# HIC15.net
KiCad netlist of a schematic drawn in Altium Designer
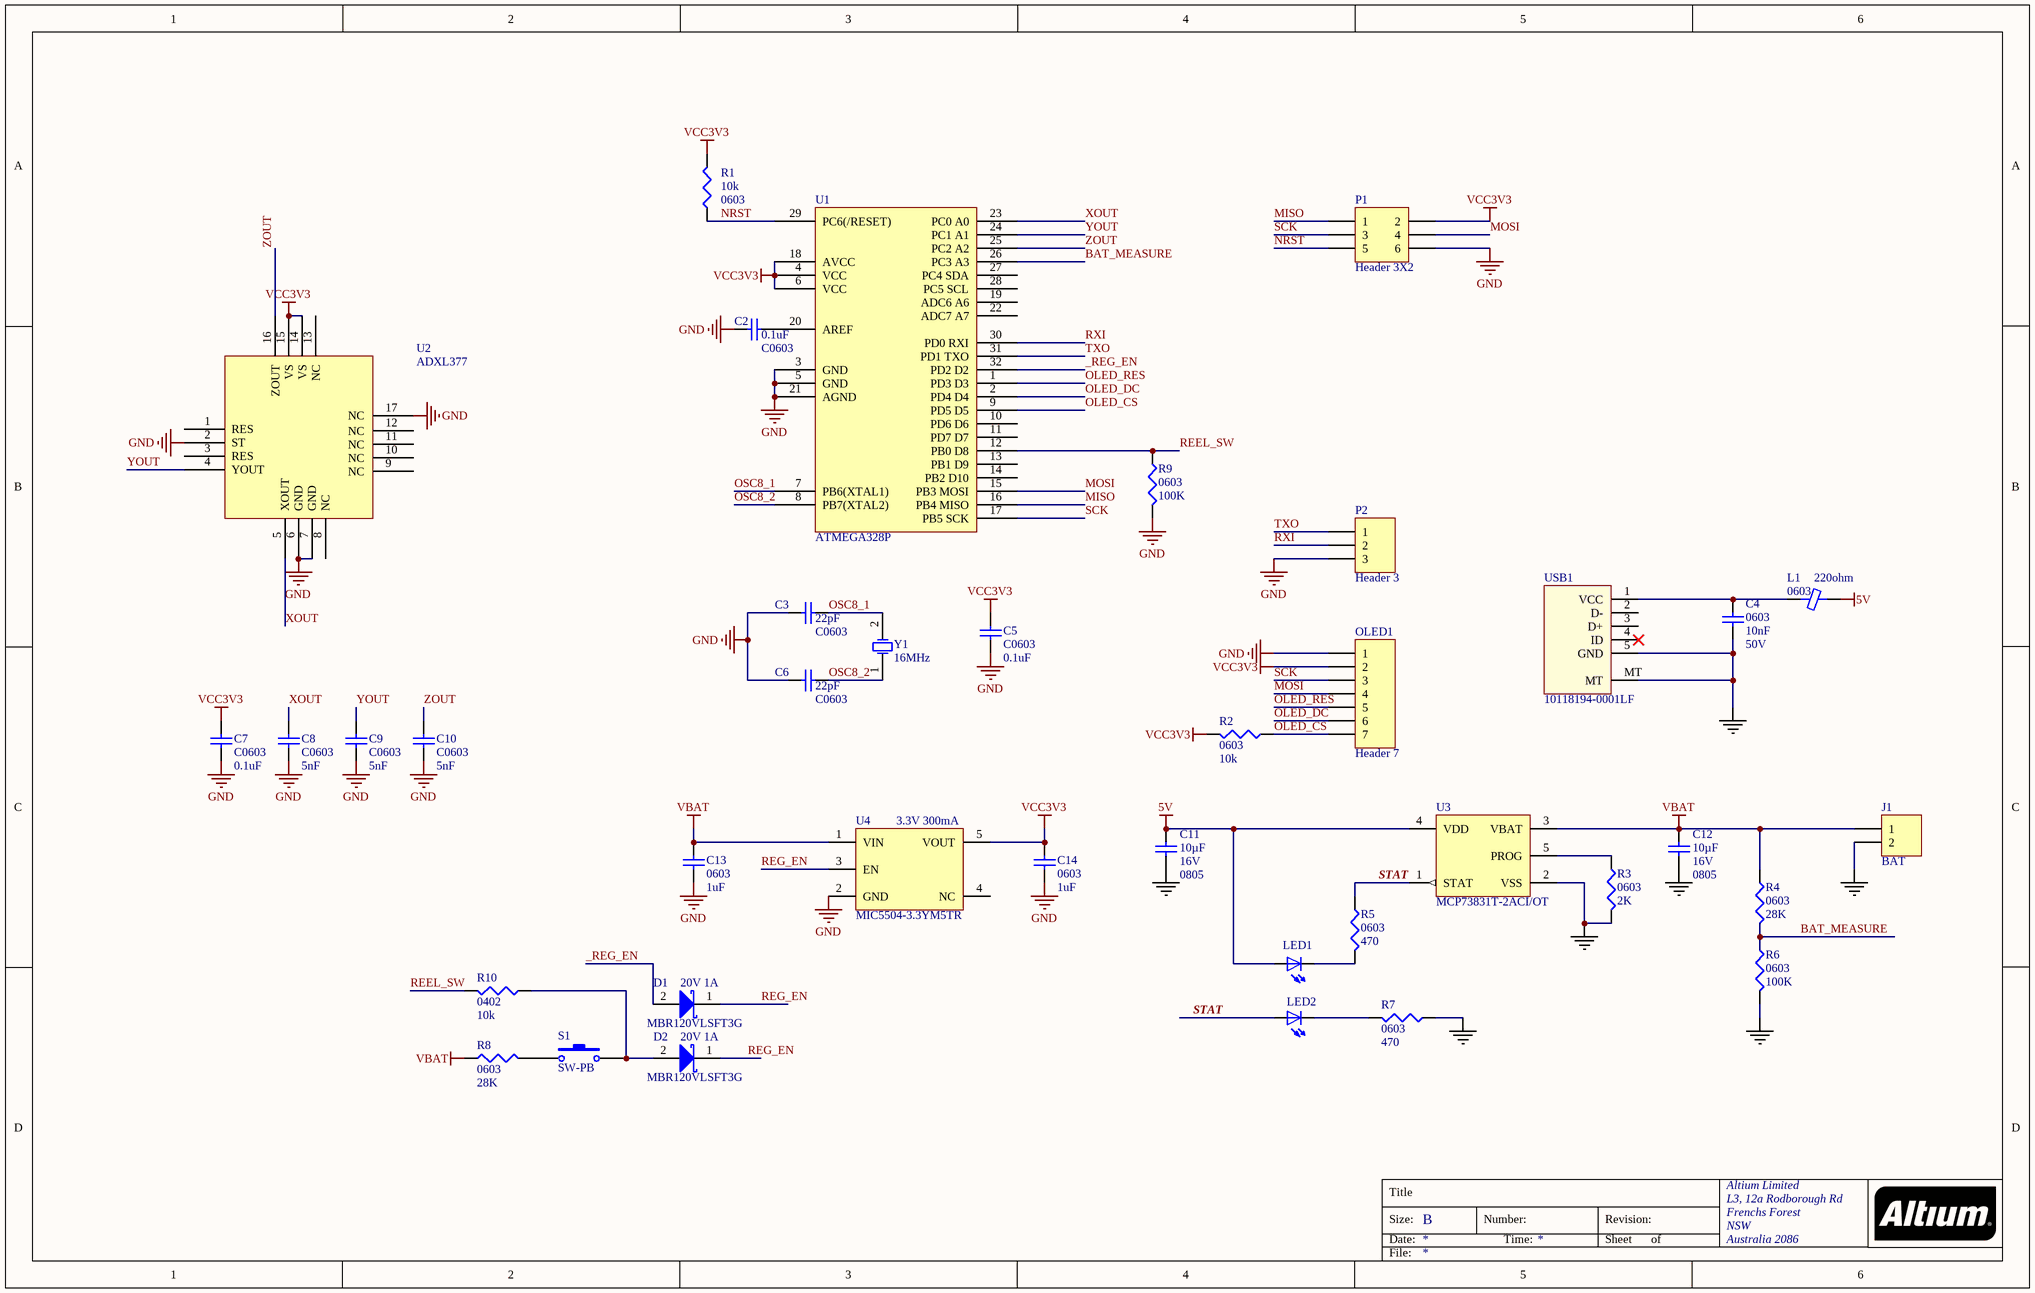
[diagram p0: HIC15.SchDoc]

(export (version "E")
  (design (tool "Eeschema 10.0.6"))
  (components
    (comp (ref "C2")
      (value "C0603")
      (footprint "C0603")
      (description "Capacitor")
      (fields (field (name "ALTIUM_VALUE") "0.1uF"))
      (libsource (lib "Miscellaneous Devices") (part "Cap_0603"))
    )
    (comp (ref "C3")
      (value "C0603")
      (footprint "C0603")
      (description "Capacitor")
      (fields (field (name "ALTIUM_VALUE") "22pF"))
      (libsource (lib "Miscellaneous Devices") (part "Cap_0603"))
    )
    (comp (ref "C4")
      (value "0603")
      (footprint "C0603")
      (description "CAP CER 10000PF 50V X7R 0402")
      (fields
        (field (name "ALTIUM_VALUE") "10nF")
        (field (name "MANUFACTURER") "Murata")
        (field (name "MANUFACTURER PART NUMBER") "GCM155R71H103KA55D")
        (field (name "VOLTAGE RATING") "50V")
      )
      (libsource (lib "Miscellaneous Devices") (part "Cap Semi"))
    )
    (comp (ref "C5")
      (value "C0603")
      (footprint "C0603")
      (description "Capacitor")
      (fields (field (name "ALTIUM_VALUE") "0.1uF"))
      (libsource (lib "Miscellaneous Devices") (part "Cap_0603"))
    )
    (comp (ref "C6")
      (value "C0603")
      (footprint "C0603")
      (description "Capacitor")
      (fields (field (name "ALTIUM_VALUE") "22pF"))
      (libsource (lib "Miscellaneous Devices") (part "Cap_0603"))
    )
    (comp (ref "C7")
      (value "C0603")
      (footprint "C0603")
      (description "Capacitor")
      (fields (field (name "ALTIUM_VALUE") "0.1uF"))
      (libsource (lib "Miscellaneous Devices") (part "Cap_0603"))
    )
    (comp (ref "C8")
      (value "C0603")
      (footprint "C0603")
      (description "Capacitor")
      (fields (field (name "ALTIUM_VALUE") "5nF"))
      (libsource (lib "Miscellaneous Devices") (part "Cap_0603"))
    )
    (comp (ref "C9")
      (value "C0603")
      (footprint "C0603")
      (description "Capacitor")
      (fields (field (name "ALTIUM_VALUE") "5nF"))
      (libsource (lib "Miscellaneous Devices") (part "Cap_0603"))
    )
    (comp (ref "C10")
      (value "C0603")
      (footprint "C0603")
      (description "Capacitor")
      (fields (field (name "ALTIUM_VALUE") "5nF"))
      (libsource (lib "Miscellaneous Devices") (part "Cap_0603"))
    )
    (comp (ref "C11")
      (value "0805")
      (footprint "C0805")
      (description "CAP CER 10UF 16V X5R 0805")
      (fields
        (field (name "ALTIUM_VALUE") "10µF")
        (field (name "MANUFACTURER") "Murata Electronics North America")
        (field (name "MANUFACTURER PART NUMBER") "GRM21BR61C106KE15K")
        (field (name "VOLTAGE - RATED") "16V")
      )
      (libsource (lib "Miscellaneous Devices") (part "Cap Semi"))
    )
    (comp (ref "C12")
      (value "0805")
      (footprint "C0805")
      (description "CAP CER 10UF 16V X5R 0805")
      (fields
        (field (name "ALTIUM_VALUE") "10µF")
        (field (name "MANUFACTURER") "Murata Electronics North America")
        (field (name "MANUFACTURER PART NUMBER") "GRM21BR61C106KE15K")
        (field (name "VOLTAGE - RATED") "16V")
      )
      (libsource (lib "Miscellaneous Devices") (part "Cap Semi"))
    )
    (comp (ref "C13")
      (value "0603")
      (footprint "C0603")
      (description "Capacitor")
      (fields (field (name "ALTIUM_VALUE") "1uF") (field (name "PUBLISHER") "Altium Limited"))
      (libsource (lib "Miscellaneous Devices") (part "Cap"))
    )
    (comp (ref "C14")
      (value "0603")
      (footprint "C0603")
      (description "Capacitor")
      (fields (field (name "ALTIUM_VALUE") "1uF") (field (name "PUBLISHER") "Altium Limited"))
      (libsource (lib "Miscellaneous Devices") (part "Cap"))
    )
    (comp (ref "D1")
      (value "MBR120VLSFT3G")
      (footprint "SOD-123FL")
      (description "DIODE SCHOTTKY 20V 1A SOD123FL")
      (fields (field (name "MANUFACTURER") "ON Semiconductor") (field (name "ALTIUM_VALUE") "20V 1A"))
      (libsource (lib "Miscellaneous Devices") (part "D Schottky"))
    )
    (comp (ref "D2")
      (value "MBR120VLSFT3G")
      (footprint "SOD-123FL")
      (description "DIODE SCHOTTKY 20V 1A SOD123FL")
      (fields (field (name "MANUFACTURER") "ON Semiconductor") (field (name "ALTIUM_VALUE") "20V 1A"))
      (libsource (lib "Miscellaneous Devices") (part "D Schottky"))
    )
    (comp (ref "J1")
      (value "BAT")
      (footprint "HDR1X2")
      (description "Header, 2-Pin")
      (fields (field (name "PUBLISHER") "Altium Limited"))
      (libsource (lib "Miscellaneous Connectors") (part "Header 2"))
    )
    (comp (ref "L1")
      (value "0603")
      (footprint "FER 0603/1608")
      (description "FERRITE BEAD 220 OHM 0603 1LN")
      (fields
        (field (name "MANUFACTURER") "Murata")
        (field (name "MANUFACTURER PART NUMBER") "BLM18EG221SN1D")
        (field (name "ALTIUM_VALUE") "220ohm")
      )
      (libsource (lib "RF Symbols") (part "Ferrite Chip"))
    )
    (comp (ref "LED1")
      (value "LTST-C190KRKT")
      (footprint "LED-0603-RED")
      (description "LED, GREEN, 0.9MM X 1.1MM, 10MCD, 570NM")
      (fields (field (name "MANUFACTURER") "Lite-On Inc."))
      (libsource (lib "DOUBLE-SIDE") (part "LED0603DWS"))
    )
    (comp (ref "LED2")
      (value "LTST-C190KGKT")
      (footprint "LED-0603-GREEN")
      (description "LED GREEN CLEAR 0603 SMD")
      (fields (field (name "MANUFACTURER") "Lite-On Inc."))
      (libsource (lib "DOUBLE-SIDE") (part "LED0603DWS"))
    )
    (comp (ref "OLED1")
      (value "Header 7")
      (footprint "CON-7")
      (description "Header, 7-Pin")
      (fields (field (name "PUBLISHER") "Altium Limited"))
      (libsource (lib "Miscellaneous Connectors") (part "Header 7"))
    )
    (comp (ref "P1")
      (value "Header 3X2")
      (footprint "SPI_PORT")
      (description "Header, 3-Pin, Dual row")
      (fields (field (name "PUBLISHER") "Altium Limited"))
      (libsource (lib "Miscellaneous Connectors") (part "Header 3X2"))
    )
    (comp (ref "P2")
      (value "Header 3")
      (footprint "HDR1X3")
      (description "Header, 3-Pin")
      (fields (field (name "PUBLISHER") "Altium Limited"))
      (libsource (lib "Miscellaneous Connectors") (part "Header 3"))
    )
    (comp (ref "R1")
      (value "0603")
      (footprint "R0603")
      (description "Resistor")
      (fields (field (name "ALTIUM_VALUE") "10k"))
      (libsource (lib "Miscellaneous Devices") (part "Res3"))
    )
    (comp (ref "R2")
      (value "0603")
      (footprint "R0603")
      (description "Resistor")
      (fields (field (name "ALTIUM_VALUE") "10k"))
      (libsource (lib "Miscellaneous Devices") (part "Res3"))
    )
    (comp (ref "R3")
      (value "0603")
      (footprint "R0603")
      (description "Resistor")
      (fields (field (name "ALTIUM_VALUE") "2K"))
      (libsource (lib "Miscellaneous Devices") (part "Res3"))
    )
    (comp (ref "R4")
      (value "0603")
      (footprint "R0603")
      (description "Resistor")
      (fields (field (name "ALTIUM_VALUE") "28K"))
      (libsource (lib "Miscellaneous Devices") (part "Res3"))
    )
    (comp (ref "R5")
      (value "0603")
      (footprint "R0603")
      (description "Resistor")
      (fields (field (name "ALTIUM_VALUE") "470"))
      (libsource (lib "Miscellaneous Devices") (part "Res3"))
    )
    (comp (ref "R6")
      (value "0603")
      (footprint "R0603")
      (description "Resistor")
      (fields (field (name "ALTIUM_VALUE") "100K"))
      (libsource (lib "Miscellaneous Devices") (part "Res3"))
    )
    (comp (ref "R7")
      (value "0603")
      (footprint "R0603")
      (description "Resistor")
      (fields (field (name "ALTIUM_VALUE") "470"))
      (libsource (lib "Miscellaneous Devices") (part "Res3"))
    )
    (comp (ref "R8")
      (value "0603")
      (footprint "R0603")
      (description "Resistor")
      (fields (field (name "ALTIUM_VALUE") "28K"))
      (libsource (lib "Miscellaneous Devices") (part "Res3"))
    )
    (comp (ref "R9")
      (value "0603")
      (footprint "R0603")
      (description "Resistor")
      (fields (field (name "ALTIUM_VALUE") "100K"))
      (libsource (lib "Miscellaneous Devices") (part "Res3"))
    )
    (comp (ref "R10")
      (value "0402")
      (footprint "R0402")
      (description "Resistor")
      (fields (field (name "ALTIUM_VALUE") "10k"))
      (libsource (lib "Miscellaneous Devices") (part "Res3"))
    )
    (comp (ref "S1")
      (value "SW-PB")
      (footprint "REED_SWITCH")
      (description "Switch")
      (fields (field (name "PUBLISHER") "Altium Limited"))
      (libsource (lib "Miscellaneous Devices") (part "SW-PB"))
    )
    (comp (ref "U1")
      (value "ATMEGA328P")
      (footprint "32A-M")
      (libsource (lib "Schlib1") (part "ATMEGA328P_AU"))
    )
    (comp (ref "U2")
      (value "ADXL377")
      (footprint "QFN50P300X300X150_HS-17L")
      (libsource (lib "Schlib1") (part "ADXL377"))
    )
    (comp (ref "U3")
      (value "MCP73831T-2ACI/OT")
      (footprint "SOT23-5")
      (description "IC CONTROLLR LI-ION 4.2V SOT23-5")
      (fields (field (name "MANUFACTURER") "Microchip Technology"))
      (libsource (lib "Symbols") (part "MCP73831T-2ACI/OT"))
    )
    (comp (ref "U4")
      (value "MIC5504-3.3YM5TR")
      (footprint "SOT23-5")
      (description "IC REG LINEAR 3.3V 300MA SOT23-5")
      (fields (field (name "MANUFACTURER") "Microchip Micrel") (field (name "ALTIUM_VALUE") "3.3V 300mA"))
      (libsource (lib "Footprints") (part "MIC5504-3.3YM5TR"))
    )
    (comp (ref "USB1")
      (value "10118194-0001LF")
      (footprint "10118194-0001LF")
      (description "CONN USB MICRO B RECPT SMT R/A")
      (fields (field (name "MANUFACTURER") "Amphenol FCI"))
      (libsource (lib "Symbols") (part "1050170001"))
    )
    (comp (ref "Y1")
      (value "16MHz")
      (footprint "ABM3")
      (description "Crystal Oscillator")
      (libsource (lib "Miscellaneous Devices") (part "XTAL"))
    )
  )
  (nets
    (net (code "1") (name "/BAT_MEASURE") (class "Default")
      (node (ref "R4") (pin "2") (pinfunction "2_2") (pintype "passive"))
      (node (ref "R6") (pin "1") (pinfunction "1_1") (pintype "passive"))
      (node (ref "U1") (pin "26") (pinfunction "PC3_A3_26") (pintype "passive"))
    )
    (net (code "2") (name "/MISO") (class "Default")
      (node (ref "P1") (pin "1") (pinfunction "1_1") (pintype "passive"))
      (node (ref "U1") (pin "16") (pinfunction "PB4_MISO_16") (pintype "passive"))
    )
    (net (code "3") (name "/MOSI") (class "Default")
      (node (ref "OLED1") (pin "4") (pinfunction "4_4") (pintype "passive"))
      (node (ref "P1") (pin "4") (pinfunction "4_4") (pintype "passive"))
      (node (ref "U1") (pin "15") (pinfunction "PB3_MOSI_15") (pintype "passive"))
    )
    (net (code "4") (name "/NRST") (class "Default")
      (node (ref "P1") (pin "5") (pinfunction "5_5") (pintype "passive"))
      (node (ref "R1") (pin "1") (pinfunction "1_1") (pintype "passive"))
      (node (ref "U1") (pin "29") (pinfunction "PC6(/RESET)_29") (pintype "passive"))
    )
    (net (code "5") (name "/OLED_CS") (class "Default")
      (node (ref "OLED1") (pin "7") (pinfunction "7_7") (pintype "passive"))
      (node (ref "R2") (pin "1") (pinfunction "1_1") (pintype "passive"))
      (node (ref "U1") (pin "9") (pinfunction "PD5_D5_9") (pintype "passive"))
    )
    (net (code "6") (name "/OLED_DC") (class "Default")
      (node (ref "OLED1") (pin "6") (pinfunction "6_6") (pintype "passive"))
      (node (ref "U1") (pin "2") (pinfunction "PD4_D4_2") (pintype "passive"))
    )
    (net (code "7") (name "/OLED_RES") (class "Default")
      (node (ref "OLED1") (pin "5") (pinfunction "5_5") (pintype "passive"))
      (node (ref "U1") (pin "1") (pinfunction "PD3_D3_1") (pintype "passive"))
    )
    (net (code "8") (name "/OSC8_1") (class "Default")
      (node (ref "C3") (pin "1") (pinfunction "1_1") (pintype "passive"))
      (node (ref "U1") (pin "7") (pinfunction "PB6(XTAL1)_7") (pintype "passive"))
      (node (ref "Y1") (pin "2") (pinfunction "OSC2_2") (pintype "passive"))
    )
    (net (code "9") (name "/OSC8_2") (class "Default")
      (node (ref "C6") (pin "1") (pinfunction "1_1") (pintype "passive"))
      (node (ref "U1") (pin "8") (pinfunction "PB7(XTAL2)_8") (pintype "passive"))
      (node (ref "Y1") (pin "1") (pinfunction "OSC1_1") (pintype "passive"))
    )
    (net (code "10") (name "/REEL_SW") (class "Default")
      (node (ref "R10") (pin "2") (pinfunction "2_2") (pintype "passive"))
      (node (ref "R9") (pin "1") (pinfunction "1_1") (pintype "passive"))
      (node (ref "U1") (pin "12") (pinfunction "PB0_D8_12") (pintype "passive"))
    )
    (net (code "11") (name "/REG_EN") (class "Default")
      (node (ref "D1") (pin "1") (pinfunction "A_1") (pintype "passive"))
      (node (ref "D2") (pin "1") (pinfunction "A_1") (pintype "passive"))
      (node (ref "U4") (pin "3") (pinfunction "EN_3") (pintype "passive"))
    )
    (net (code "12") (name "/RXI") (class "Default")
      (node (ref "P2") (pin "2") (pinfunction "2_2") (pintype "passive"))
      (node (ref "U1") (pin "30") (pinfunction "PD0_RXI_30") (pintype "passive"))
    )
    (net (code "13") (name "/SCK") (class "Default")
      (node (ref "OLED1") (pin "3") (pinfunction "3_3") (pintype "passive"))
      (node (ref "P1") (pin "3") (pinfunction "3_3") (pintype "passive"))
      (node (ref "U1") (pin "17") (pinfunction "PB5_SCK_17") (pintype "passive"))
    )
    (net (code "14") (name "/STAT") (class "Default")
      (node (ref "LED2") (pin "A") (pinfunction "A_A") (pintype "passive"))
      (node (ref "R5") (pin "1") (pinfunction "1_1") (pintype "passive"))
      (node (ref "U3") (pin "1") (pinfunction "STAT_1") (pintype "output"))
    )
    (net (code "15") (name "/TXO") (class "Default")
      (node (ref "P2") (pin "1") (pinfunction "1_1") (pintype "passive"))
      (node (ref "U1") (pin "31") (pinfunction "PD1_TXO_31") (pintype "passive"))
    )
    (net (code "16") (name "/XOUT") (class "Default")
      (node (ref "C8") (pin "1") (pinfunction "1_1") (pintype "passive"))
      (node (ref "U1") (pin "23") (pinfunction "PC0_A0_23") (pintype "passive"))
      (node (ref "U2") (pin "5") (pinfunction "XOUT_5") (pintype "passive"))
    )
    (net (code "17") (name "/YOUT") (class "Default")
      (node (ref "C9") (pin "1") (pinfunction "1_1") (pintype "passive"))
      (node (ref "U1") (pin "24") (pinfunction "PC1_A1_24") (pintype "passive"))
      (node (ref "U2") (pin "4") (pinfunction "YOUT_4") (pintype "passive"))
    )
    (net (code "18") (name "/ZOUT") (class "Default")
      (node (ref "C10") (pin "1") (pinfunction "1_1") (pintype "passive"))
      (node (ref "U1") (pin "25") (pinfunction "PC2_A2_25") (pintype "passive"))
      (node (ref "U2") (pin "16") (pinfunction "ZOUT_16") (pintype "passive"))
    )
    (net (code "19") (name "/_REG_EN") (class "Default")
      (node (ref "D1") (pin "2") (pinfunction "K_2") (pintype "passive"))
      (node (ref "U1") (pin "32") (pinfunction "PD2_D2_32") (pintype "passive"))
    )
    (net (code "20") (name "5V") (class "Default")
      (node (ref "C11") (pin "2") (pinfunction "2_2") (pintype "passive"))
      (node (ref "L1") (pin "1") (pinfunction "1_1") (pintype "passive"))
      (node (ref "LED1") (pin "A") (pinfunction "A_A") (pintype "passive"))
      (node (ref "U3") (pin "4") (pinfunction "VDD_4") (pintype "power_in"))
    )
    (net (code "21") (name "GND") (class "Default")
      (node (ref "C10") (pin "2") (pinfunction "2_2") (pintype "passive"))
      (node (ref "C11") (pin "1") (pinfunction "1_1") (pintype "passive"))
      (node (ref "C12") (pin "1") (pinfunction "1_1") (pintype "passive"))
      (node (ref "C13") (pin "1") (pinfunction "1_1") (pintype "passive"))
      (node (ref "C14") (pin "1") (pinfunction "1_1") (pintype "passive"))
      (node (ref "C2") (pin "2") (pinfunction "2_2") (pintype "passive"))
      (node (ref "C3") (pin "2") (pinfunction "2_2") (pintype "passive"))
      (node (ref "C4") (pin "1") (pinfunction "1_1") (pintype "passive"))
      (node (ref "C5") (pin "2") (pinfunction "2_2") (pintype "passive"))
      (node (ref "C6") (pin "2") (pinfunction "2_2") (pintype "passive"))
      (node (ref "C7") (pin "2") (pinfunction "2_2") (pintype "passive"))
      (node (ref "C8") (pin "2") (pinfunction "2_2") (pintype "passive"))
      (node (ref "C9") (pin "2") (pinfunction "2_2") (pintype "passive"))
      (node (ref "J1") (pin "2") (pinfunction "2_2") (pintype "passive"))
      (node (ref "OLED1") (pin "1") (pinfunction "1_1") (pintype "passive"))
      (node (ref "P1") (pin "6") (pinfunction "6_6") (pintype "passive"))
      (node (ref "P2") (pin "3") (pinfunction "3_3") (pintype "passive"))
      (node (ref "R3") (pin "2") (pinfunction "2_2") (pintype "passive"))
      (node (ref "R6") (pin "2") (pinfunction "2_2") (pintype "passive"))
      (node (ref "R7") (pin "1") (pinfunction "1_1") (pintype "passive"))
      (node (ref "R9") (pin "2") (pinfunction "2_2") (pintype "passive"))
      (node (ref "U1") (pin "21") (pinfunction "AGND_21") (pintype "passive"))
      (node (ref "U1") (pin "3") (pinfunction "GND_3") (pintype "passive"))
      (node (ref "U1") (pin "5") (pinfunction "GND_5") (pintype "passive"))
      (node (ref "U2") (pin "17") (pinfunction "NC_17") (pintype "passive"))
      (node (ref "U2") (pin "2") (pinfunction "ST_2") (pintype "passive"))
      (node (ref "U2") (pin "6") (pinfunction "GND_6") (pintype "passive"))
      (node (ref "U2") (pin "7") (pinfunction "GND_7") (pintype "passive"))
      (node (ref "U3") (pin "2") (pinfunction "VSS_2") (pintype "power_in"))
      (node (ref "U4") (pin "2") (pinfunction "GND_2") (pintype "passive"))
      (node (ref "USB1") (pin "5") (pinfunction "GND_5") (pintype "passive"))
      (node (ref "USB1") (pin "MT") (pinfunction "MT_MT") (pintype "passive"))
    )
    (net (code "22") (name "Net-(D2-K)") (class "Default")
      (node (ref "D2") (pin "2") (pinfunction "K_2") (pintype "passive"))
      (node (ref "R10") (pin "1") (pinfunction "1_1") (pintype "passive"))
      (node (ref "S1") (pin "2") (pinfunction "2_2") (pintype "passive"))
    )
    (net (code "23") (name "Net-(LED1-PadC)") (class "Default")
      (node (ref "LED1") (pin "C") (pinfunction "C_C") (pintype "passive"))
      (node (ref "R5") (pin "2") (pinfunction "2_2") (pintype "passive"))
    )
    (net (code "24") (name "Net-(LED2-PadC)") (class "Default")
      (node (ref "LED2") (pin "C") (pinfunction "C_C") (pintype "passive"))
      (node (ref "R7") (pin "2") (pinfunction "2_2") (pintype "passive"))
    )
    (net (code "25") (name "Net-(R8-Pad2)") (class "Default")
      (node (ref "R8") (pin "2") (pinfunction "2_2") (pintype "passive"))
      (node (ref "S1") (pin "1") (pinfunction "1_1") (pintype "passive"))
    )
    (net (code "26") (name "Net-(U1-AREF)") (class "Default")
      (node (ref "C2") (pin "1") (pinfunction "1_1") (pintype "passive"))
      (node (ref "U1") (pin "20") (pinfunction "AREF_20") (pintype "passive"))
    )
    (net (code "27") (name "Net-(U3-PROG)") (class "Default")
      (node (ref "R3") (pin "1") (pinfunction "1_1") (pintype "passive"))
      (node (ref "U3") (pin "5") (pinfunction "PROG_5") (pintype "passive"))
    )
    (net (code "28") (name "Net-(USB1-VCC)") (class "Default")
      (node (ref "C4") (pin "2") (pinfunction "2_2") (pintype "passive"))
      (node (ref "L1") (pin "2") (pinfunction "2_2") (pintype "passive"))
      (node (ref "USB1") (pin "1") (pinfunction "VCC_1") (pintype "passive"))
    )
    (net (code "29") (name "VBAT") (class "Default")
      (node (ref "C12") (pin "2") (pinfunction "2_2") (pintype "passive"))
      (node (ref "C13") (pin "2") (pinfunction "2_2") (pintype "passive"))
      (node (ref "J1") (pin "1") (pinfunction "1_1") (pintype "passive"))
      (node (ref "R4") (pin "1") (pinfunction "1_1") (pintype "passive"))
      (node (ref "R8") (pin "1") (pinfunction "1_1") (pintype "passive"))
      (node (ref "U3") (pin "3") (pinfunction "VBAT_3") (pintype "power_in"))
      (node (ref "U4") (pin "1") (pinfunction "VIN_1") (pintype "passive"))
    )
    (net (code "30") (name "VCC3V3") (class "Default")
      (node (ref "C14") (pin "2") (pinfunction "2_2") (pintype "passive"))
      (node (ref "C5") (pin "1") (pinfunction "1_1") (pintype "passive"))
      (node (ref "C7") (pin "1") (pinfunction "1_1") (pintype "passive"))
      (node (ref "OLED1") (pin "2") (pinfunction "2_2") (pintype "passive"))
      (node (ref "P1") (pin "2") (pinfunction "2_2") (pintype "passive"))
      (node (ref "R1") (pin "2") (pinfunction "2_2") (pintype "passive"))
      (node (ref "R2") (pin "2") (pinfunction "2_2") (pintype "passive"))
      (node (ref "U1") (pin "18") (pinfunction "AVCC_18") (pintype "passive"))
      (node (ref "U1") (pin "4") (pinfunction "VCC_4") (pintype "passive"))
      (node (ref "U1") (pin "6") (pinfunction "VCC_6") (pintype "passive"))
      (node (ref "U2") (pin "14") (pinfunction "VS_14") (pintype "passive"))
      (node (ref "U2") (pin "15") (pinfunction "VS_15") (pintype "passive"))
      (node (ref "U4") (pin "5") (pinfunction "VOUT_5") (pintype "passive"))
    )
    (net (code "31") (name "unconnected-(U1-ADC6_A6-Pad19)") (class "Default")
      (node (ref "U1") (pin "19") (pinfunction "ADC6_A6_19") (pintype "passive"))
    )
    (net (code "32") (name "unconnected-(U1-ADC7_A7-Pad22)") (class "Default")
      (node (ref "U1") (pin "22") (pinfunction "ADC7_A7_22") (pintype "passive"))
    )
    (net (code "33") (name "unconnected-(U1-PB1_D9-Pad13)") (class "Default")
      (node (ref "U1") (pin "13") (pinfunction "PB1_D9_13") (pintype "passive"))
    )
    (net (code "34") (name "unconnected-(U1-PB2_D10-Pad14)") (class "Default")
      (node (ref "U1") (pin "14") (pinfunction "PB2_D10_14") (pintype "passive"))
    )
    (net (code "35") (name "unconnected-(U1-PC4_SDA-Pad27)") (class "Default")
      (node (ref "U1") (pin "27") (pinfunction "PC4_SDA_27") (pintype "passive"))
    )
    (net (code "36") (name "unconnected-(U1-PC5_SCL-Pad28)") (class "Default")
      (node (ref "U1") (pin "28") (pinfunction "PC5_SCL_28") (pintype "passive"))
    )
    (net (code "37") (name "unconnected-(U1-PD6_D6-Pad10)") (class "Default")
      (node (ref "U1") (pin "10") (pinfunction "PD6_D6_10") (pintype "passive"))
    )
    (net (code "38") (name "unconnected-(U1-PD7_D7-Pad11)") (class "Default")
      (node (ref "U1") (pin "11") (pinfunction "PD7_D7_11") (pintype "passive"))
    )
    (net (code "39") (name "unconnected-(U2-NC-Pad8)") (class "Default")
      (node (ref "U2") (pin "8") (pinfunction "NC_8") (pintype "passive"))
    )
    (net (code "40") (name "unconnected-(U2-NC-Pad9)") (class "Default")
      (node (ref "U2") (pin "9") (pinfunction "NC_9") (pintype "passive"))
    )
    (net (code "41") (name "unconnected-(U2-NC-Pad10)") (class "Default")
      (node (ref "U2") (pin "10") (pinfunction "NC_10") (pintype "passive"))
    )
    (net (code "42") (name "unconnected-(U2-NC-Pad11)") (class "Default")
      (node (ref "U2") (pin "11") (pinfunction "NC_11") (pintype "passive"))
    )
    (net (code "43") (name "unconnected-(U2-NC-Pad12)") (class "Default")
      (node (ref "U2") (pin "12") (pinfunction "NC_12") (pintype "passive"))
    )
    (net (code "44") (name "unconnected-(U2-NC-Pad13)") (class "Default")
      (node (ref "U2") (pin "13") (pinfunction "NC_13") (pintype "passive"))
    )
    (net (code "45") (name "unconnected-(U2-RES-Pad1)") (class "Default")
      (node (ref "U2") (pin "1") (pinfunction "RES_1") (pintype "passive"))
    )
    (net (code "46") (name "unconnected-(U2-RES-Pad3)") (class "Default")
      (node (ref "U2") (pin "3") (pinfunction "RES_3") (pintype "passive"))
    )
    (net (code "47") (name "unconnected-(U4-NC-Pad4)") (class "Default")
      (node (ref "U4") (pin "4") (pinfunction "NC_4") (pintype "passive"))
    )
    (net (code "48") (name "unconnected-(USB1-D+-Pad3)") (class "Default")
      (node (ref "USB1") (pin "3") (pinfunction "D+_3") (pintype "passive"))
    )
    (net (code "49") (name "unconnected-(USB1-D--Pad2)") (class "Default")
      (node (ref "USB1") (pin "2") (pinfunction "D-_2") (pintype "passive"))
    )
    (net (code "50") (name "unconnected-(USB1-ID-Pad4)") (class "Default")
      (node (ref "USB1") (pin "4") (pinfunction "ID_4") (pintype "passive+no_connect"))
    )
  )
)
